# Schematic.net
KiCad netlist of a schematic drawn in EAGLE
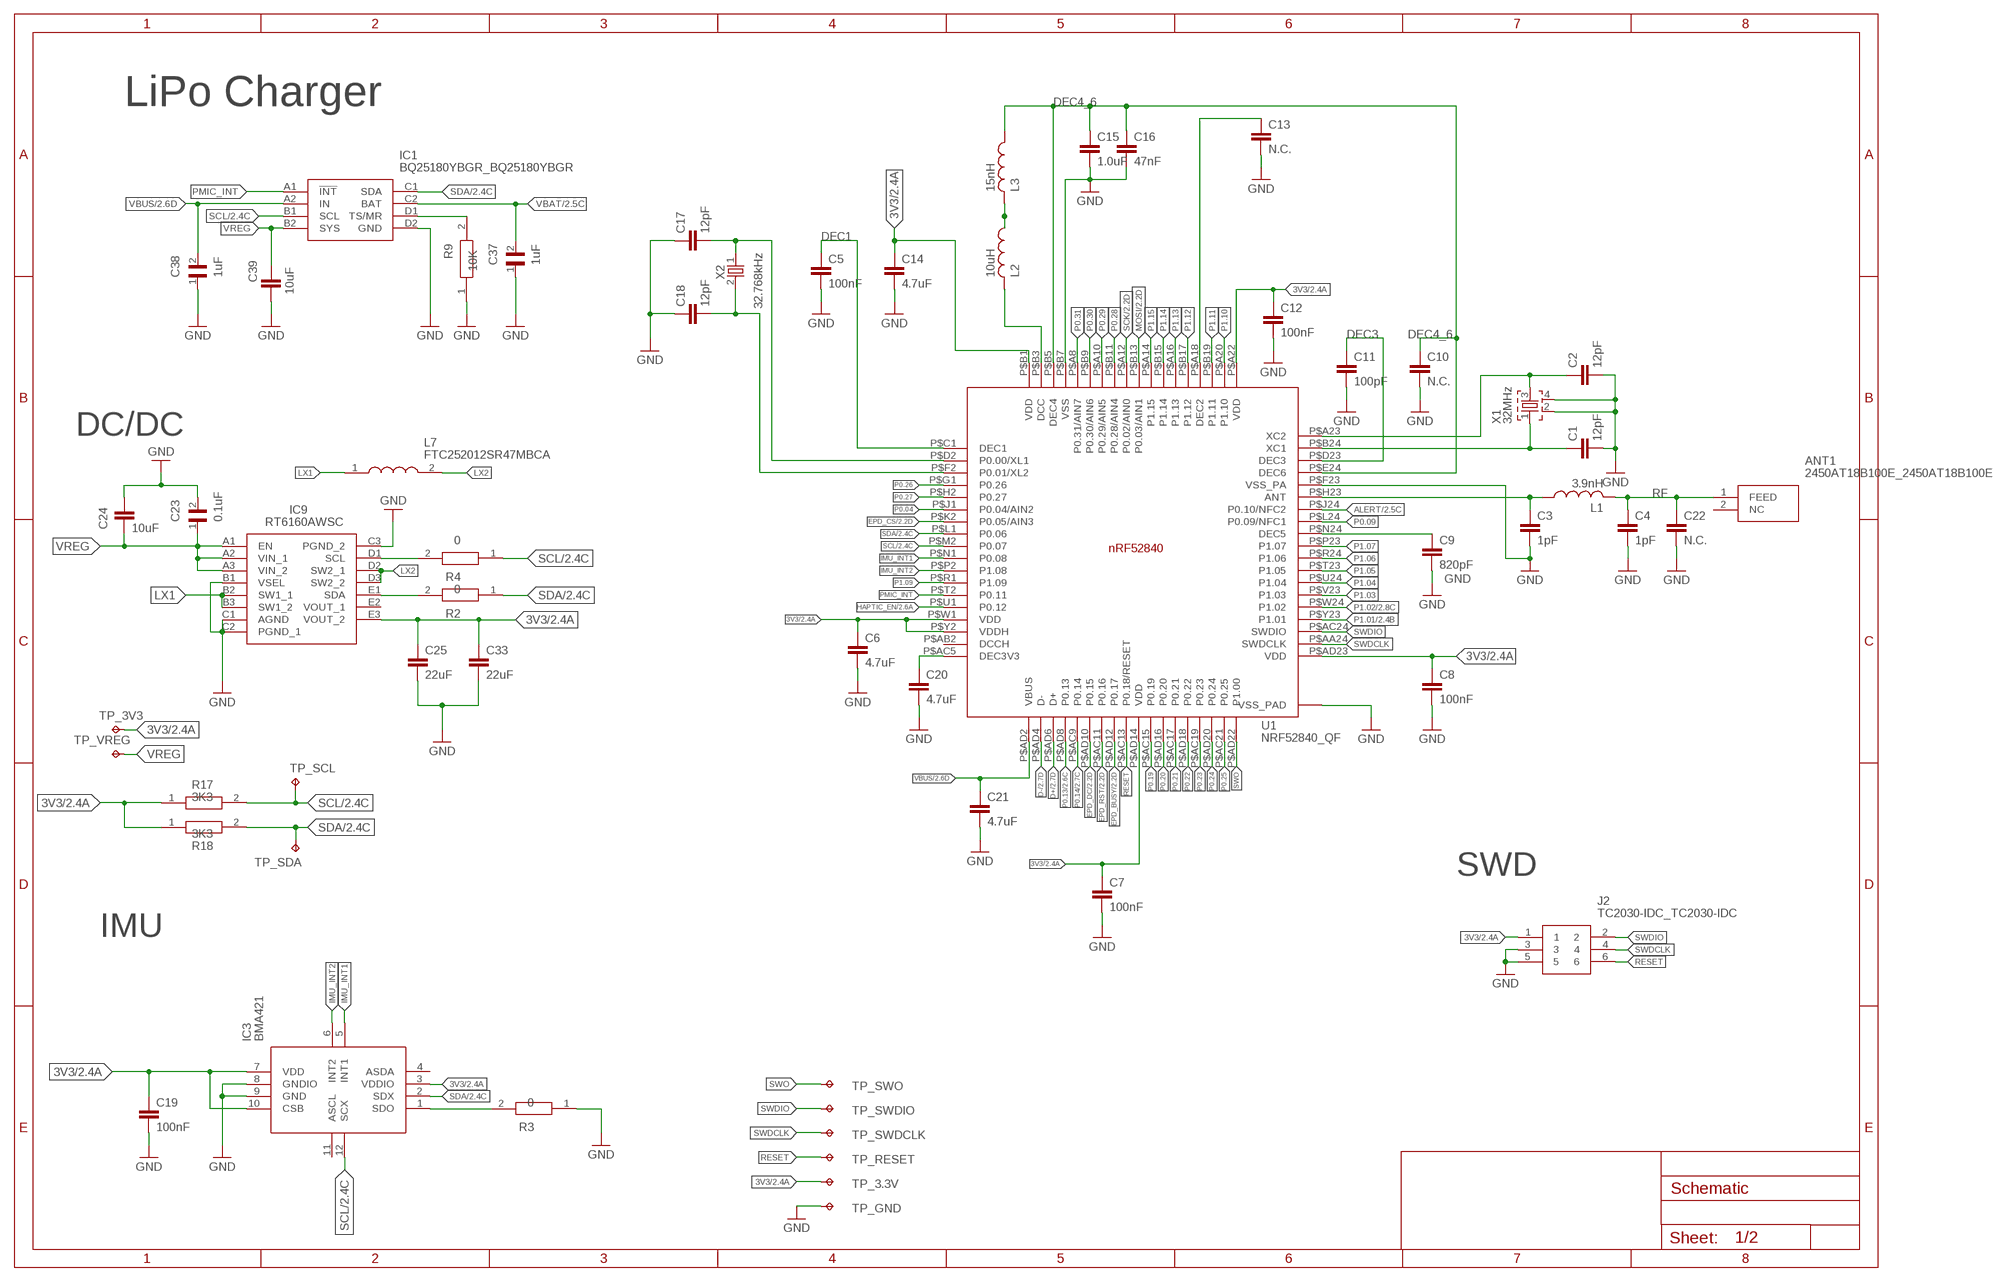
[diagram p0: schematic, sheet 1]
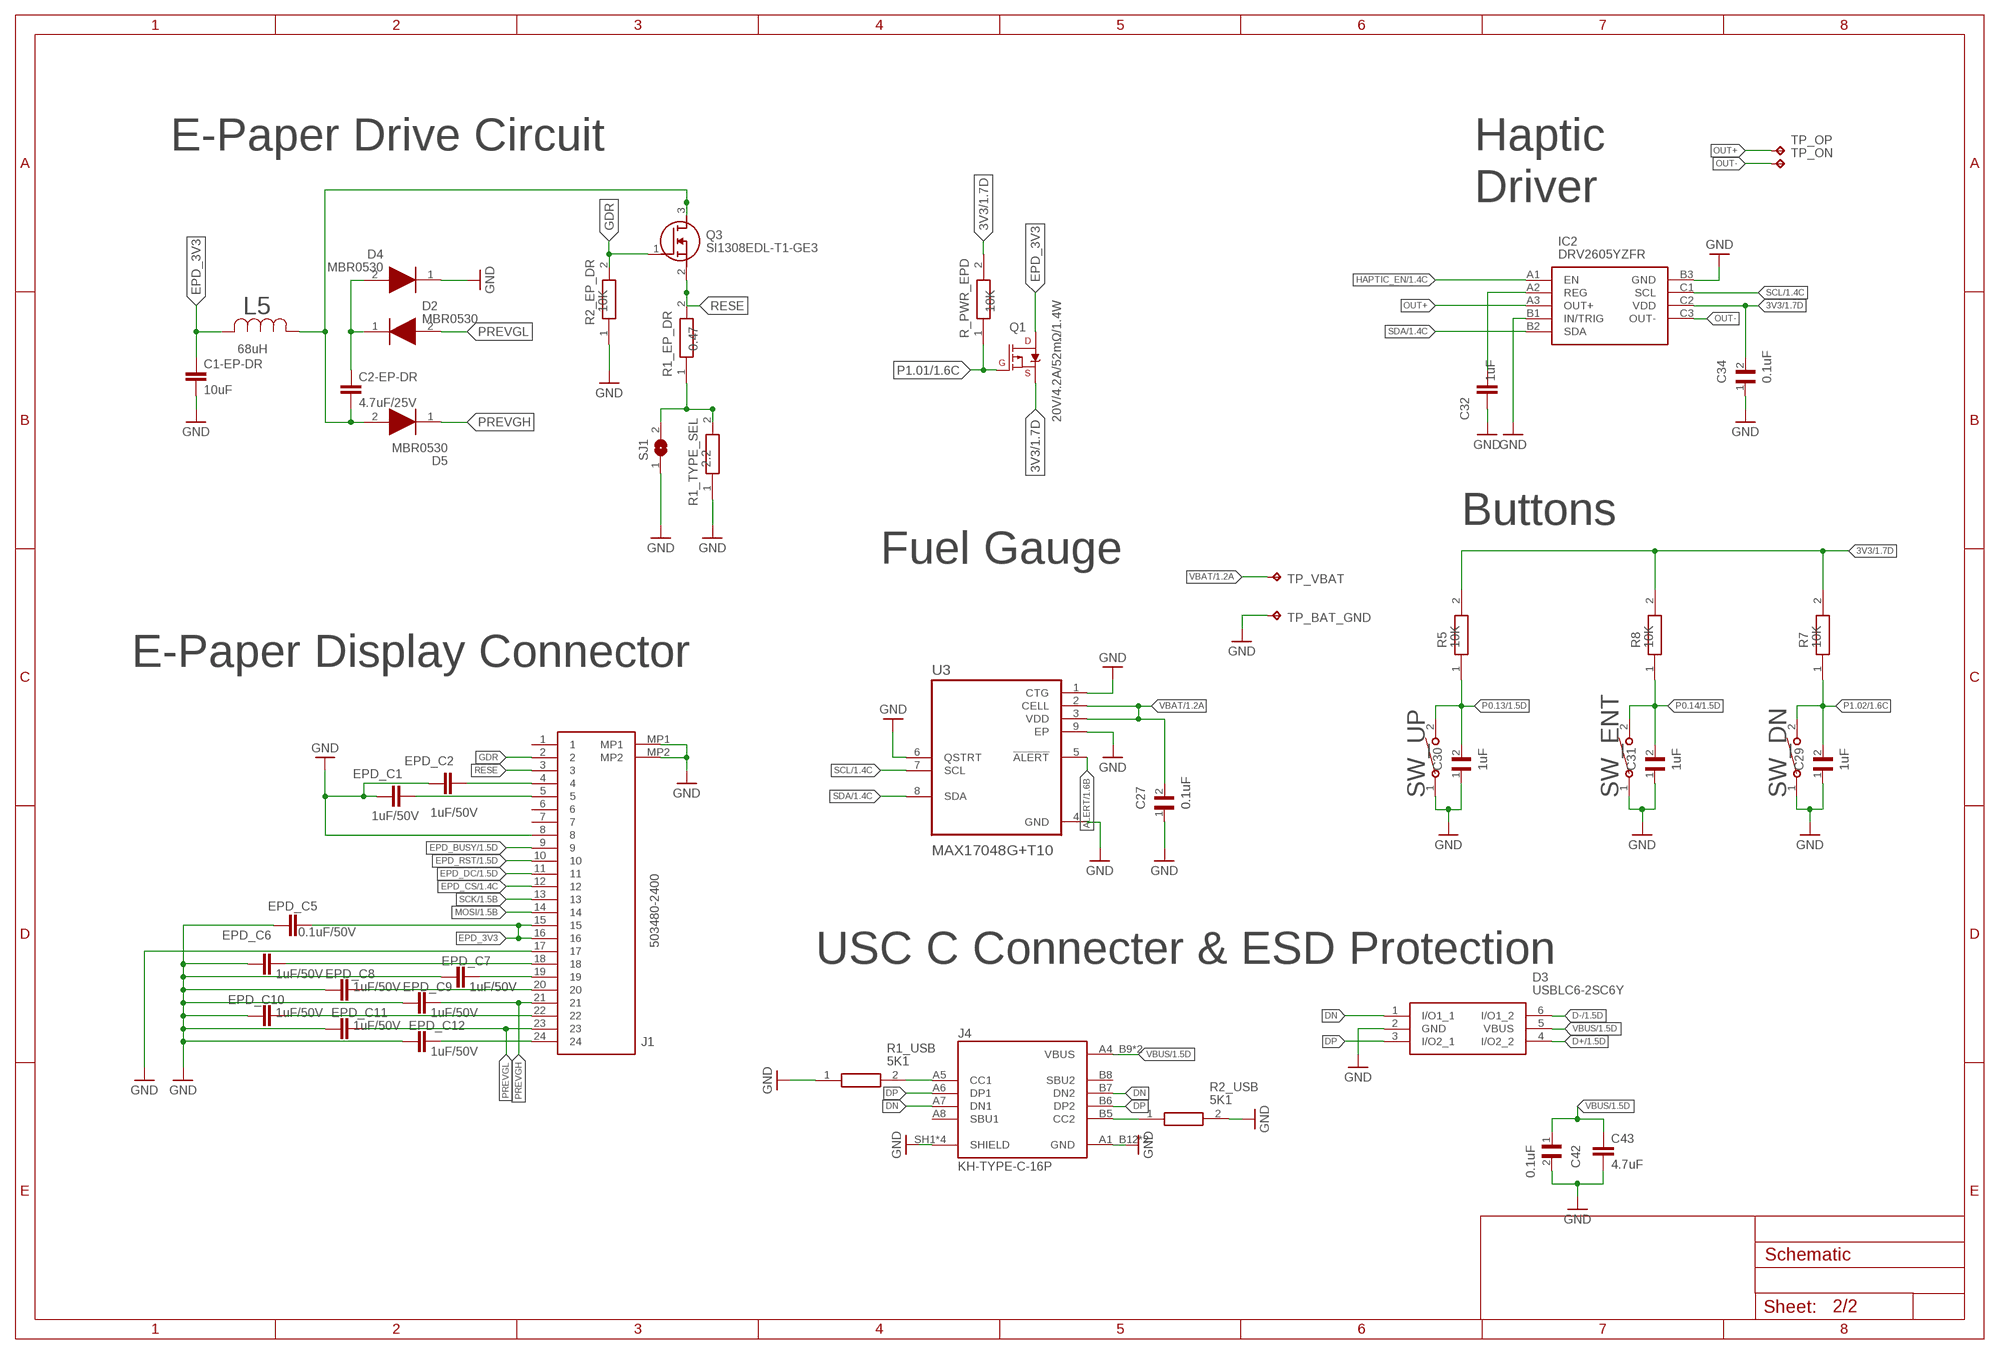
[diagram p1: schematic, sheet 2]

(export (version "E")
  (design (tool "Eeschema 10.0.6"))
  (components
    (comp (ref "ANT1")
      (value "2450AT18B100E_2450AT18B100E")
      (footprint "eagle-import:2450AT18B100E_ANTC3216X140N")
      (fields
        (field (name "ARROW_PART_NUMBER") "2450AT18B100E")
        (field (name "MOUSER_PART_NUMBER") "609-2450AT18B100E")
      )
      (libsource (lib "eagle-import") (part "2450AT18B100E_2450AT18B100E"))
    )
    (comp (ref "C1")
      (value "12pF")
      (footprint "eagle-import:NORDIC_NRF_3_RESC0201_L")
      (libsource (lib "eagle-import") (part "NORDIC_NRF_3_CAPACITOR_0201_L"))
    )
    (comp (ref "C2")
      (value "12pF")
      (footprint "eagle-import:NORDIC_NRF_3_RESC0201_L")
      (libsource (lib "eagle-import") (part "NORDIC_NRF_3_CAPACITOR_0201_L"))
    )
    (comp (ref "C3")
      (value "1pF")
      (footprint "eagle-import:NORDIC_NRF_3_RESC0201_L")
      (libsource (lib "eagle-import") (part "NORDIC_NRF_3_CAPACITOR_0201_L"))
    )
    (comp (ref "C4")
      (value "1pF")
      (footprint "eagle-import:NORDIC_NRF_3_RESC0201_L")
      (libsource (lib "eagle-import") (part "NORDIC_NRF_3_CAPACITOR_0201_L"))
    )
    (comp (ref "C5")
      (value "100nF")
      (footprint "eagle-import:NORDIC_NRF_3_RESC0201_L")
      (libsource (lib "eagle-import") (part "NORDIC_NRF_3_CAPACITOR_0201_L"))
    )
    (comp (ref "C6")
      (value "4.7uF")
      (footprint "eagle-import:NORDIC_NRF_3_RESC0402_L")
      (libsource (lib "eagle-import") (part "NORDIC_NRF_3_CAPACITOR_0402_L"))
    )
    (comp (ref "C7")
      (value "100nF")
      (footprint "eagle-import:NORDIC_NRF_3_RESC0201_L")
      (libsource (lib "eagle-import") (part "NORDIC_NRF_3_CAPACITOR_0201_L"))
    )
    (comp (ref "C8")
      (value "100nF")
      (footprint "eagle-import:NORDIC_NRF_3_RESC0201_L")
      (libsource (lib "eagle-import") (part "NORDIC_NRF_3_CAPACITOR_0201_L"))
    )
    (comp (ref "C9")
      (value "820pF")
      (footprint "eagle-import:NORDIC_NRF_3_RESC0201_L")
      (libsource (lib "eagle-import") (part "NORDIC_NRF_3_CAPACITOR_0201_L"))
    )
    (comp (ref "C10")
      (value "N.C.")
      (footprint "eagle-import:NORDIC_NRF_3_RESC0201_L")
      (libsource (lib "eagle-import") (part "NORDIC_NRF_3_CAPACITOR_0201_L"))
    )
    (comp (ref "C11")
      (value "100pF")
      (footprint "eagle-import:NORDIC_NRF_3_RESC0201_L")
      (libsource (lib "eagle-import") (part "NORDIC_NRF_3_CAPACITOR_0201_L"))
    )
    (comp (ref "C12")
      (value "100nF")
      (footprint "eagle-import:NORDIC_NRF_3_RESC0201_L")
      (libsource (lib "eagle-import") (part "NORDIC_NRF_3_CAPACITOR_0201_L"))
    )
    (comp (ref "C13")
      (value "N.C.")
      (footprint "eagle-import:NORDIC_NRF_3_RESC0201_L")
      (libsource (lib "eagle-import") (part "NORDIC_NRF_3_CAPACITOR_0201_L"))
    )
    (comp (ref "C14")
      (value "4.7uF")
      (footprint "eagle-import:NORDIC_NRF_3_RESC0402_L")
      (libsource (lib "eagle-import") (part "NORDIC_NRF_3_CAPACITOR_0402_L"))
    )
    (comp (ref "C15")
      (value "1.0uF")
      (footprint "eagle-import:NORDIC_NRF_3_RESC0402_L")
      (libsource (lib "eagle-import") (part "NORDIC_NRF_3_CAPACITOR_0402_L"))
    )
    (comp (ref "C16")
      (value "47nF")
      (footprint "eagle-import:NORDIC_NRF_3_RESC0201_L")
      (libsource (lib "eagle-import") (part "NORDIC_NRF_3_CAPACITOR_0201_L"))
    )
    (comp (ref "C17")
      (value "12pF")
      (footprint "eagle-import:NORDIC_NRF_3_RESC0201_L")
      (libsource (lib "eagle-import") (part "NORDIC_NRF_3_CAPACITOR_0201_L"))
    )
    (comp (ref "C18")
      (value "12pF")
      (footprint "eagle-import:NORDIC_NRF_3_RESC0201_L")
      (libsource (lib "eagle-import") (part "NORDIC_NRF_3_CAPACITOR_0201_L"))
    )
    (comp (ref "C19")
      (value "100nF")
      (footprint "eagle-import:NORDIC_NRF_3_RESC0201_L")
      (libsource (lib "eagle-import") (part "NORDIC_NRF_3_CAPACITOR_0201_L"))
    )
    (comp (ref "C20")
      (value "4.7uF")
      (footprint "eagle-import:NORDIC_NRF_3_RESC0402_L")
      (libsource (lib "eagle-import") (part "NORDIC_NRF_3_CAPACITOR_0402_L"))
    )
    (comp (ref "C21")
      (value "4.7uF")
      (footprint "eagle-import:NORDIC_NRF_3_RESC0402_L")
      (libsource (lib "eagle-import") (part "NORDIC_NRF_3_CAPACITOR_0402_L"))
    )
    (comp (ref "C22")
      (value "N.C.")
      (footprint "eagle-import:NORDIC_NRF_3_RESC0201_L")
      (libsource (lib "eagle-import") (part "NORDIC_NRF_3_CAPACITOR_0201_L"))
    )
    (comp (ref "C23")
      (value "0.1uF")
      (footprint "eagle-import:GRM011R60J152KE01L_2_CAPC0201X13N")
      (fields (field (name "MF") "Murata") (field (name "MP") "GRM011R60J152KE01L"))
      (libsource (lib "eagle-import") (part "GRM011R60J152KE01L_2_GRM011R60J152KE01L"))
    )
    (comp (ref "C24")
      (value "10uF")
      (footprint "eagle-import:NORDIC_NRF_3_RESC0402_L")
      (libsource (lib "eagle-import") (part "NORDIC_NRF_3_CAPACITOR_0402_L"))
    )
    (comp (ref "C25")
      (value "22uF")
      (footprint "eagle-import:NORDIC_NRF_3_RESC0402_L")
      (libsource (lib "eagle-import") (part "NORDIC_NRF_3_CAPACITOR_0402_L"))
    )
    (comp (ref "C33")
      (value "22uF")
      (footprint "eagle-import:NORDIC_NRF_3_RESC0402_L")
      (libsource (lib "eagle-import") (part "NORDIC_NRF_3_CAPACITOR_0402_L"))
    )
    (comp (ref "C37")
      (value "1uF")
      (footprint "eagle-import:GRM011R60J152KE01L_2_CAPC0201X13N")
      (fields (field (name "MF") "Murata") (field (name "MP") "GRM011R60J152KE01L"))
      (libsource (lib "eagle-import") (part "GRM011R60J152KE01L_2_GRM011R60J152KE01L"))
    )
    (comp (ref "C38")
      (value "1uF")
      (footprint "eagle-import:GRM011R60J152KE01L_2_CAPC0201X13N")
      (fields (field (name "MF") "Murata") (field (name "MP") "GRM011R60J152KE01L"))
      (libsource (lib "eagle-import") (part "GRM011R60J152KE01L_2_GRM011R60J152KE01L"))
    )
    (comp (ref "C39")
      (value "10uF")
      (footprint "eagle-import:NORDIC_NRF_3_RESC0402_N")
      (libsource (lib "eagle-import") (part "NORDIC_NRF_3_CAPACITOR_0402_N"))
    )
    (comp (ref "IC1")
      (value "BQ25180YBGR_BQ25180YBGR")
      (footprint "eagle-import:BQ25180YBGR_BGA8C40P2X4_100X155X50")
      (fields
        (field (name "ARROW_PART_NUMBER") "BQ25180YBGR")
        (field (name "MOUSER_PART_NUMBER") "595-BQ25180YBGR")
      )
      (libsource (lib "eagle-import") (part "BQ25180YBGR_BQ25180YBGR"))
    )
    (comp (ref "IC3")
      (value "BMA421")
      (footprint "eagle-import:BMA423_BMA423")
      (fields (field (name "ARROW_PART_NUMBER") "BMA423") (field (name "MOUSER_PART_NUMBER") "262-BMA423"))
      (libsource (lib "eagle-import") (part "BMA423_BMA423"))
    )
    (comp (ref "IC9")
      (value "RT6160AWSC")
      (footprint "eagle-import:RT6160AWSC_BGA15C40P3X5_140X230X60")
      (fields (field (name "MOUSER_PART_NUMBER") "835-RT6160AWSC"))
      (libsource (lib "eagle-import") (part "RT6160AWSC_RT6160AWSC"))
    )
    (comp (ref "J2")
      (value "TC2030-IDC_TC2030-IDC")
      (footprint "eagle-import:TC2030-IDC_TC2030IDC")
      (fields (field (name "MANUFACTURER_PART_NUMBER") "TC2030-IDC"))
      (libsource (lib "eagle-import") (part "TC2030-IDC_TC2030-IDC"))
    )
    (comp (ref "L1")
      (value "3.9nH")
      (footprint "eagle-import:NORDIC_NRF_2_RESC0402_L")
      (libsource (lib "eagle-import") (part "NORDIC_NRF_2_INDUCTOR_0402_L"))
    )
    (comp (ref "L2")
      (value "10uH")
      (footprint "eagle-import:NORDIC_NRF_2_RESC0402_L")
      (libsource (lib "eagle-import") (part "NORDIC_NRF_2_INDUCTOR_0402_L"))
    )
    (comp (ref "L3")
      (value "15nH")
      (footprint "eagle-import:NORDIC_NRF_2_RESC0402_L")
      (libsource (lib "eagle-import") (part "NORDIC_NRF_2_INDUCTOR_0402_L"))
    )
    (comp (ref "L7")
      (value "FTC252012SR47MBCA")
      (footprint "eagle-import:MLP2016SR47MT0S1_INDC2016X100N")
      (libsource (lib "eagle-import") (part "MLP2016SR47MT0S1_FTC252012SR47MBCA"))
    )
    (comp (ref "R2")
      (value "0")
      (footprint "eagle-import:ERA-1AEB3401C_0201")
      (libsource (lib "eagle-import") (part "ERA-1AEB3401C_CPF0201D7K68C1"))
    )
    (comp (ref "R3")
      (value "0")
      (footprint "eagle-import:CPF0201D7K68C1_0201")
      (libsource (lib "eagle-import") (part "CPF0201D7K68C1_CPF0201D7K68C1"))
    )
    (comp (ref "R4")
      (value "0")
      (footprint "eagle-import:ERA-1AEB3401C_0201")
      (libsource (lib "eagle-import") (part "ERA-1AEB3401C_CPF0201D7K68C1"))
    )
    (comp (ref "R9")
      (value "10K")
      (footprint "eagle-import:CPF0201D7K68C1_0201")
      (libsource (lib "eagle-import") (part "CPF0201D7K68C1_CPF0201D7K68C1"))
    )
    (comp (ref "R17")
      (value "3K3")
      (footprint "eagle-import:CPF0201D7K68C1_0201")
      (libsource (lib "eagle-import") (part "CPF0201D7K68C1_CPF0201D7K68C1"))
    )
    (comp (ref "R18")
      (value "3K3")
      (footprint "eagle-import:CPF0201D7K68C1_0201")
      (libsource (lib "eagle-import") (part "CPF0201D7K68C1_CPF0201D7K68C1"))
    )
    (comp (ref "TP_3.3V")
      (value "HECTOR_WATCH_1_TPTP20R")
      (footprint "eagle-import:HECTOR_WATCH_1_TP20R")
      (libsource (lib "eagle-import") (part "HECTOR_WATCH_1_TPTP20R"))
    )
    (comp (ref "TP_3V3")
      (value "HECTOR_WATCH_1_TPTP20R")
      (footprint "eagle-import:HECTOR_WATCH_1_TP20R")
      (libsource (lib "eagle-import") (part "HECTOR_WATCH_1_TPTP20R"))
    )
    (comp (ref "TP_GND")
      (value "HECTOR_WATCH_1_TPTP20R")
      (footprint "eagle-import:HECTOR_WATCH_1_TP20R")
      (libsource (lib "eagle-import") (part "HECTOR_WATCH_1_TPTP20R"))
    )
    (comp (ref "TP_RESET")
      (value "HECTOR_WATCH_1_TPTP20R")
      (footprint "eagle-import:HECTOR_WATCH_1_TP20R")
      (libsource (lib "eagle-import") (part "HECTOR_WATCH_1_TPTP20R"))
    )
    (comp (ref "TP_SCL")
      (value "HECTOR_WATCH_1_TPTP20R")
      (footprint "eagle-import:HECTOR_WATCH_1_TP20R")
      (libsource (lib "eagle-import") (part "HECTOR_WATCH_1_TPTP20R"))
    )
    (comp (ref "TP_SDA")
      (value "HECTOR_WATCH_1_TPTP20R")
      (footprint "eagle-import:HECTOR_WATCH_1_TP20R")
      (libsource (lib "eagle-import") (part "HECTOR_WATCH_1_TPTP20R"))
    )
    (comp (ref "TP_SWDCLK")
      (value "HECTOR_WATCH_1_TPTP20R")
      (footprint "eagle-import:HECTOR_WATCH_1_TP20R")
      (libsource (lib "eagle-import") (part "HECTOR_WATCH_1_TPTP20R"))
    )
    (comp (ref "TP_SWDIO")
      (value "HECTOR_WATCH_1_TPTP20R")
      (footprint "eagle-import:HECTOR_WATCH_1_TP20R")
      (libsource (lib "eagle-import") (part "HECTOR_WATCH_1_TPTP20R"))
    )
    (comp (ref "TP_SWO")
      (value "HECTOR_WATCH_1_TPTP20R")
      (footprint "eagle-import:HECTOR_WATCH_1_TP20R")
      (libsource (lib "eagle-import") (part "HECTOR_WATCH_1_TPTP20R"))
    )
    (comp (ref "TP_VREG")
      (value "HECTOR_WATCH_1_TPTP20R")
      (footprint "eagle-import:HECTOR_WATCH_1_TP20R")
      (libsource (lib "eagle-import") (part "HECTOR_WATCH_1_TPTP20R"))
    )
    (comp (ref "U1")
      (value "NRF52840_QF")
      (footprint "eagle-import:NORDIC_NRF_4_AQFN50P700X700X85_HS-74N")
      (libsource (lib "eagle-import") (part "NORDIC_NRF_4_NRF52840_QF"))
    )
    (comp (ref "X1")
      (value "32MHz")
      (footprint "eagle-import:NORDIC_NRF_BT-XTAL_2016_N")
      (libsource (lib "eagle-import") (part "NORDIC_NRF_XTAL_32MHZ"))
    )
    (comp (ref "X2")
      (value "32.768kHz")
      (footprint "eagle-import:NORDIC_NRF_1_XTAL_3215_N")
      (libsource (lib "eagle-import") (part "NORDIC_NRF_1_XTAL_32KHZ"))
    )
    (comp (ref "C1-EP-DR")
      (value "10uF")
      (footprint "eagle-import:NORDIC_NRF_3_RESC0402_L")
      (libsource (lib "eagle-import") (part "NORDIC_NRF_3_CAPACITOR_0402_L"))
    )
    (comp (ref "C2-EP-DR")
      (value "4.7uF/25V")
      (footprint "eagle-import:NORDIC_NRF_3_RESC0201_L")
      (libsource (lib "eagle-import") (part "NORDIC_NRF_3_CAPACITOR_0201_L"))
    )
    (comp (ref "C27")
      (value "0.1uF")
      (footprint "eagle-import:GRM011R60J152KE01L_2_CAPC0201X13N")
      (fields (field (name "MF") "Murata") (field (name "MP") "GRM011R60J152KE01L"))
      (libsource (lib "eagle-import") (part "GRM011R60J152KE01L_2_GRM011R60J152KE01L"))
    )
    (comp (ref "C29")
      (value "1uF")
      (footprint "eagle-import:GRM011R60J152KE01L_2_CAPC0201X13N")
      (fields (field (name "MF") "Murata") (field (name "MP") "GRM011R60J152KE01L"))
      (libsource (lib "eagle-import") (part "GRM011R60J152KE01L_2_GRM011R60J152KE01L"))
    )
    (comp (ref "C30")
      (value "1uF")
      (footprint "eagle-import:GRM011R60J152KE01L_2_CAPC0201X13N")
      (fields (field (name "MF") "Murata") (field (name "MP") "GRM011R60J152KE01L"))
      (libsource (lib "eagle-import") (part "GRM011R60J152KE01L_2_GRM011R60J152KE01L"))
    )
    (comp (ref "C31")
      (value "1uF")
      (footprint "eagle-import:GRM011R60J152KE01L_2_CAPC0201X13N")
      (fields (field (name "MF") "Murata") (field (name "MP") "GRM011R60J152KE01L"))
      (libsource (lib "eagle-import") (part "GRM011R60J152KE01L_2_GRM011R60J152KE01L"))
    )
    (comp (ref "C32")
      (value "1uF")
      (footprint "eagle-import:NORDIC_NRF_3_RESC0402_L")
      (libsource (lib "eagle-import") (part "NORDIC_NRF_3_CAPACITOR_0402_L"))
    )
    (comp (ref "C34")
      (value "0.1uF")
      (footprint "eagle-import:GRM011R60J152KE01L_2_CAPC0201X13N")
      (fields (field (name "MF") "Murata") (field (name "MP") "GRM011R60J152KE01L"))
      (libsource (lib "eagle-import") (part "GRM011R60J152KE01L_2_GRM011R60J152KE01L"))
    )
    (comp (ref "C42")
      (value "0.1uF")
      (footprint "eagle-import:GRM011R60J152KE01L_2_CAPC0201X13N")
      (fields (field (name "MF") "Murata") (field (name "MP") "GRM011R60J152KE01L"))
      (libsource (lib "eagle-import") (part "GRM011R60J152KE01L_2_GRM011R60J152KE01L"))
    )
    (comp (ref "C43")
      (value "4.7uF")
      (footprint "eagle-import:NORDIC_NRF_3_RESC0402_L")
      (libsource (lib "eagle-import") (part "NORDIC_NRF_3_CAPACITOR_0402_L"))
    )
    (comp (ref "D2")
      (value "MBR0530")
      (footprint "eagle-import:ESP32_C6_LIBRARY_5_SOD3716X135N")
      (fields (field (name "MF") "ON Semiconductor"))
      (libsource (lib "eagle-import") (part "ESP32_C6_LIBRARY_5_MBR0530"))
    )
    (comp (ref "D3")
      (value "USBLC6-2SC6Y")
      (footprint "eagle-import:ESP32_C6_LIBRARY_3_SOT95P280X145-6N")
      (fields (field (name "MF") "STMicroelectronics"))
      (libsource (lib "eagle-import") (part "ESP32_C6_LIBRARY_3_USBLC6-2SC6Y"))
    )
    (comp (ref "D4")
      (value "MBR0530")
      (footprint "eagle-import:ESP32_C6_LIBRARY_5_SOD3716X135N")
      (fields (field (name "MF") "ON Semiconductor"))
      (libsource (lib "eagle-import") (part "ESP32_C6_LIBRARY_5_MBR0530"))
    )
    (comp (ref "D5")
      (value "MBR0530")
      (footprint "eagle-import:ESP32_C6_LIBRARY_5_SOD3716X135N")
      (fields (field (name "MF") "ON Semiconductor"))
      (libsource (lib "eagle-import") (part "ESP32_C6_LIBRARY_5_MBR0530"))
    )
    (comp (ref "EPD_C1")
      (value "1uF/50V")
      (footprint "eagle-import:NORDIC_NRF_3_RESC0402_L")
      (libsource (lib "eagle-import") (part "NORDIC_NRF_3_CAPACITOR_0402_L"))
    )
    (comp (ref "EPD_C2")
      (value "1uF/50V")
      (footprint "eagle-import:NORDIC_NRF_3_RESC0402_L")
      (libsource (lib "eagle-import") (part "NORDIC_NRF_3_CAPACITOR_0402_L"))
    )
    (comp (ref "EPD_C5")
      (value "0.1uF/50V")
      (footprint "eagle-import:NORDIC_NRF_3_RESC0402_L")
      (libsource (lib "eagle-import") (part "NORDIC_NRF_3_CAPACITOR_0402_L"))
    )
    (comp (ref "EPD_C6")
      (value "1uF/50V")
      (footprint "eagle-import:NORDIC_NRF_3_RESC0402_L")
      (libsource (lib "eagle-import") (part "NORDIC_NRF_3_CAPACITOR_0402_L"))
    )
    (comp (ref "EPD_C7")
      (value "1uF/50V")
      (footprint "eagle-import:NORDIC_NRF_3_RESC0402_L")
      (libsource (lib "eagle-import") (part "NORDIC_NRF_3_CAPACITOR_0402_L"))
    )
    (comp (ref "EPD_C8")
      (value "1uF/50V")
      (footprint "eagle-import:NORDIC_NRF_3_RESC0402_L")
      (libsource (lib "eagle-import") (part "NORDIC_NRF_3_CAPACITOR_0402_L"))
    )
    (comp (ref "EPD_C9")
      (value "1uF/50V")
      (footprint "eagle-import:NORDIC_NRF_3_RESC0402_L")
      (libsource (lib "eagle-import") (part "NORDIC_NRF_3_CAPACITOR_0402_L"))
    )
    (comp (ref "EPD_C10")
      (value "1uF/50V")
      (footprint "eagle-import:NORDIC_NRF_3_RESC0402_L")
      (libsource (lib "eagle-import") (part "NORDIC_NRF_3_CAPACITOR_0402_L"))
    )
    (comp (ref "EPD_C11")
      (value "1uF/50V")
      (footprint "eagle-import:NORDIC_NRF_3_RESC0402_L")
      (libsource (lib "eagle-import") (part "NORDIC_NRF_3_CAPACITOR_0402_L"))
    )
    (comp (ref "EPD_C12")
      (value "1uF/50V")
      (footprint "eagle-import:NORDIC_NRF_3_RESC0402_L")
      (libsource (lib "eagle-import") (part "NORDIC_NRF_3_CAPACITOR_0402_L"))
    )
    (comp (ref "IC2")
      (value "DRV2605YZFR")
      (footprint "eagle-import:DRV2605YZFR_BGA9C50P3X3_144X144X62")
      (libsource (lib "eagle-import") (part "DRV2605YZFR_DRV2605YZFR"))
    )
    (comp (ref "J1")
      (value "503480-2400")
      (footprint "eagle-import:503480-2400_5034802400")
      (fields (field (name "MOUSER_PART_NUMBER") "538-503480-2400"))
      (libsource (lib "eagle-import") (part "503480-2400_503480-2400"))
    )
    (comp (ref "J4")
      (value "KH-TYPE-C-16P")
      (footprint "eagle-import:KH-TYPE-C-16P_KINGHELM_KH-TYPE-C-16P")
      (fields (field (name "MF") "kinghelm"))
      (libsource (lib "eagle-import") (part "KH-TYPE-C-16P_KH-TYPE-C-16P"))
    )
    (comp (ref "L5")
      (value "68uH")
      (footprint "eagle-import:ESP32_C6_LIBRARY_2_IND_4828-WE-TPC_WRE")
      (fields
        (field (name "MANUFACTURER_PART_NUMBER") "744043680")
        (field (name "COPYRIGHT") "Copyright (C) 2024 Ultra Librarian. All rights reserved.")
      )
      (libsource (lib "eagle-import") (part "ESP32_C6_LIBRARY_2_744043680IND_4828-WE-TPC_WRE"))
    )
    (comp (ref "Q1")
      (value "20V/4.2A/52mΩ/1.4W")
      (footprint "eagle-import:ESP32_C6_LIBRARY_4_ESP32_C6_LIBRARY_4_ESP32_C6_LIBRARY_4_ESP32_C6_LIBRARY_4_ESP32_WROVER_SPARKFUN-DISCRETESEMI_SOT23-3")
      (libsource (lib "eagle-import") (part "ESP32_C6_LIBRARY_4_ESP32_WROVER_SPARKFUN-DISCRETESEMI_MOSFET_PCH-DMG2305UX-7"))
    )
    (comp (ref "Q3")
      (value "SI1308EDL-T1-GE3")
      (footprint "eagle-import:ESP32_C6_LIBRARY_6_SOT65P210X110-3N")
      (fields (field (name "MF") "Vishay Siliconix"))
      (libsource (lib "eagle-import") (part "ESP32_C6_LIBRARY_6_SI1308EDL-T1-GE3"))
    )
    (comp (ref "R1_EP_DR")
      (value "0.47")
      (footprint "eagle-import:CPF0201D7K68C1_0201")
      (libsource (lib "eagle-import") (part "CPF0201D7K68C1_CPF0201D7K68C1"))
    )
    (comp (ref "R1_TYPE_SEL")
      (value "2.2")
      (footprint "eagle-import:CPF0201D7K68C1_0201")
      (libsource (lib "eagle-import") (part "CPF0201D7K68C1_CPF0201D7K68C1"))
    )
    (comp (ref "R1_USB")
      (value "5K1")
      (footprint "eagle-import:ERA-1AEB3401C_0201")
      (libsource (lib "eagle-import") (part "ERA-1AEB3401C_CPF0201D7K68C1"))
    )
    (comp (ref "R2_EP_DR")
      (value "10K")
      (footprint "eagle-import:CPF0201D7K68C1_0201")
      (libsource (lib "eagle-import") (part "CPF0201D7K68C1_CPF0201D7K68C1"))
    )
    (comp (ref "R2_USB")
      (value "5K1")
      (footprint "eagle-import:CPF0201D7K68C1_0201")
      (libsource (lib "eagle-import") (part "CPF0201D7K68C1_CPF0201D7K68C1"))
    )
    (comp (ref "R5")
      (value "10K")
      (footprint "eagle-import:ERA-1AEB3401C_0201")
      (libsource (lib "eagle-import") (part "ERA-1AEB3401C_CPF0201D7K68C1"))
    )
    (comp (ref "R7")
      (value "10K")
      (footprint "eagle-import:ERA-1AEB3401C_0201")
      (libsource (lib "eagle-import") (part "ERA-1AEB3401C_CPF0201D7K68C1"))
    )
    (comp (ref "R8")
      (value "10K")
      (footprint "eagle-import:ERA-1AEB3401C_0201")
      (libsource (lib "eagle-import") (part "ERA-1AEB3401C_CPF0201D7K68C1"))
    )
    (comp (ref "R_PWR_EPD")
      (value "10K")
      (footprint "eagle-import:CPF0201D7K68C1_0201")
      (libsource (lib "eagle-import") (part "CPF0201D7K68C1_CPF0201D7K68C1"))
    )
    (comp (ref "SJ1")
      (value "ESP32_C6_LIBRARY_7_JUMPER_SJ")
      (footprint "eagle-import:ESP32_C6_LIBRARY_7_JUMPER_SJ")
      (libsource (lib "eagle-import") (part "ESP32_C6_LIBRARY_7_JUMPER_SJ"))
    )
    (comp (ref "SW_DN")
      (value "2025-10-22_07-23-44_LIBRARY_EVP-AKE31ASW_EVP-AKE31A_PAN")
      (footprint "eagle-import:2025-10-22_07-23-44_LIBRARY_SW_EVP-AKE31A_PAN")
      (fields
        (field (name "MANUFACTURER_PART_NUMBER") "EVP-AKE31A")
        (field (name "COPYRIGHT") "Copyright (C) 2025 Ultra Librarian. All rights reserved.")
      )
      (libsource (lib "eagle-import") (part "2025-10-22_07-23-44_LIBRARY_EVP-AKE31ASW_EVP-AKE31A_PAN"))
    )
    (comp (ref "SW_ENT")
      (value "2025-10-22_07-23-44_LIBRARY_EVP-AKE31ASW_EVP-AKE31A_PAN")
      (footprint "eagle-import:2025-10-22_07-23-44_LIBRARY_SW_EVP-AKE31A_PAN")
      (fields
        (field (name "MANUFACTURER_PART_NUMBER") "EVP-AKE31A")
        (field (name "COPYRIGHT") "Copyright (C) 2025 Ultra Librarian. All rights reserved.")
      )
      (libsource (lib "eagle-import") (part "2025-10-22_07-23-44_LIBRARY_EVP-AKE31ASW_EVP-AKE31A_PAN"))
    )
    (comp (ref "SW_UP")
      (value "2025-10-22_07-23-44_LIBRARY_EVP-AKE31ASW_EVP-AKE31A_PAN")
      (footprint "eagle-import:2025-10-22_07-23-44_LIBRARY_SW_EVP-AKE31A_PAN")
      (fields
        (field (name "MANUFACTURER_PART_NUMBER") "EVP-AKE31A")
        (field (name "COPYRIGHT") "Copyright (C) 2025 Ultra Librarian. All rights reserved.")
      )
      (libsource (lib "eagle-import") (part "2025-10-22_07-23-44_LIBRARY_EVP-AKE31ASW_EVP-AKE31A_PAN"))
    )
    (comp (ref "TP_BAT_GND")
      (value "HECTOR_WATCH_1_TPTP20R")
      (footprint "eagle-import:HECTOR_WATCH_1_TP20R")
      (libsource (lib "eagle-import") (part "HECTOR_WATCH_1_TPTP20R"))
    )
    (comp (ref "TP_ON")
      (value "HECTOR_WATCH_1_TPTP20R")
      (footprint "eagle-import:HECTOR_WATCH_1_TP20R")
      (libsource (lib "eagle-import") (part "HECTOR_WATCH_1_TPTP20R"))
    )
    (comp (ref "TP_OP")
      (value "HECTOR_WATCH_1_TPTP20R")
      (footprint "eagle-import:HECTOR_WATCH_1_TP20R")
      (libsource (lib "eagle-import") (part "HECTOR_WATCH_1_TPTP20R"))
    )
    (comp (ref "TP_VBAT")
      (value "HECTOR_WATCH_1_TPTP20R")
      (footprint "eagle-import:HECTOR_WATCH_1_TP20R")
      (libsource (lib "eagle-import") (part "HECTOR_WATCH_1_TPTP20R"))
    )
    (comp (ref "U3")
      (value "MAX17048G+T10")
      (footprint "eagle-import:ESP32_C6_LIBRARY_SON50P200X200X80-9N")
      (fields (field (name "MF") "Analog Devices"))
      (libsource (lib "eagle-import") (part "ESP32_C6_LIBRARY_MAX17048G+T10"))
    )
  )
  (nets
    (net (code "1") (name "3V3{slash}1.7D") (class "Default")
      (node (ref "C34") (pin "2") (pinfunction "2_2") (pintype "passive"))
      (node (ref "IC2") (pin "C2") (pinfunction "VDD_C2") (pintype "bidirectional"))
      (node (ref "Q1") (pin "2") (pinfunction "S_2") (pintype "bidirectional"))
      (node (ref "R5") (pin "2") (pinfunction "2_2") (pintype "bidirectional"))
      (node (ref "R7") (pin "2") (pinfunction "2_2") (pintype "bidirectional"))
      (node (ref "R8") (pin "2") (pinfunction "2_2") (pintype "bidirectional"))
      (node (ref "R_PWR_EPD") (pin "2") (pinfunction "2_2") (pintype "bidirectional"))
    )
    (net (code "2") (name "3V3{slash}2.4A") (class "Default")
      (node (ref "C12") (pin "1") (pinfunction "1_1") (pintype "passive"))
      (node (ref "C14") (pin "1") (pinfunction "1_1") (pintype "passive"))
      (node (ref "C19") (pin "1") (pinfunction "1_1") (pintype "passive"))
      (node (ref "C25") (pin "1") (pinfunction "1_1") (pintype "passive"))
      (node (ref "C33") (pin "1") (pinfunction "1_1") (pintype "passive"))
      (node (ref "C6") (pin "1") (pinfunction "1_1") (pintype "passive"))
      (node (ref "C7") (pin "1") (pinfunction "1_1") (pintype "passive"))
      (node (ref "C8") (pin "1") (pinfunction "1_1") (pintype "passive"))
      (node (ref "IC3") (pin "10") (pinfunction "CSB_10") (pintype "bidirectional"))
      (node (ref "IC3") (pin "3") (pinfunction "VDDIO_3") (pintype "bidirectional"))
      (node (ref "IC3") (pin "7") (pinfunction "VDD_7") (pintype "bidirectional"))
      (node (ref "IC9") (pin "E3") (pinfunction "VOUT_2_E3") (pintype "bidirectional"))
      (node (ref "J2") (pin "1") (pinfunction "1_1") (pintype "bidirectional"))
      (node (ref "R17") (pin "1") (pinfunction "1_1") (pintype "bidirectional"))
      (node (ref "R18") (pin "1") (pinfunction "1_1") (pintype "bidirectional"))
      (node (ref "TP_3.3V") (pin "TP") (pinfunction "TP_TP") (pintype "input"))
      (node (ref "TP_3V3") (pin "TP") (pinfunction "TP_TP") (pintype "input"))
      (node (ref "U1") (pin "P$A22") (pinfunction "VDD_P$A22") (pintype "power_in"))
      (node (ref "U1") (pin "P$AD14") (pinfunction "VDD_P$AD14") (pintype "power_in"))
      (node (ref "U1") (pin "P$AD23") (pinfunction "VDD_P$AD23") (pintype "power_in"))
      (node (ref "U1") (pin "P$B1") (pinfunction "VDD_P$B1") (pintype "power_in"))
      (node (ref "U1") (pin "P$W1") (pinfunction "VDD_P$W1") (pintype "power_in"))
      (node (ref "U1") (pin "P$Y2") (pinfunction "VDDH_P$Y2") (pintype "power_in"))
    )
    (net (code "3") (name "ALERT") (class "Default")
      (node (ref "U1") (pin "P$J24") (pinfunction "P0.10/NFC2_P$J24") (pintype "bidirectional"))
      (node (ref "U3") (pin "5") (pinfunction "~{ALERT}_5") (pintype "output"))
    )
    (net (code "4") (name "D+") (class "Default")
      (node (ref "D3") (pin "4") (pinfunction "I/O2_2_4") (pintype "bidirectional"))
      (node (ref "U1") (pin "P$AD6") (pinfunction "D+_P$AD6") (pintype "bidirectional"))
    )
    (net (code "5") (name "D-") (class "Default")
      (node (ref "D3") (pin "6") (pinfunction "I/O1_2_6") (pintype "bidirectional"))
      (node (ref "U1") (pin "P$AD4") (pinfunction "D-_P$AD4") (pintype "bidirectional"))
    )
    (net (code "6") (name "DEC1") (class "Default")
      (node (ref "C5") (pin "1") (pinfunction "1_1") (pintype "passive"))
      (node (ref "U1") (pin "P$C1") (pinfunction "DEC1_P$C1") (pintype "power_in"))
    )
    (net (code "7") (name "DEC3") (class "Default")
      (node (ref "C11") (pin "1") (pinfunction "1_1") (pintype "passive"))
      (node (ref "U1") (pin "P$D23") (pinfunction "DEC3_P$D23") (pintype "bidirectional"))
    )
    (net (code "8") (name "DEC4_6") (class "Default")
      (node (ref "C10") (pin "1") (pinfunction "1_1") (pintype "passive"))
      (node (ref "C15") (pin "1") (pinfunction "1_1") (pintype "passive"))
      (node (ref "C16") (pin "1") (pinfunction "1_1") (pintype "passive"))
      (node (ref "L3") (pin "1") (pinfunction "1_1") (pintype "passive"))
      (node (ref "U1") (pin "P$B5") (pinfunction "DEC4_P$B5") (pintype "power_in"))
      (node (ref "U1") (pin "P$E24") (pinfunction "DEC6_P$E24") (pintype "bidirectional"))
    )
    (net (code "9") (name "DN") (class "Default")
      (node (ref "D3") (pin "1") (pinfunction "I/O1_1_1") (pintype "bidirectional"))
      (node (ref "J4") (pin "A7") (pinfunction "DN1_A7") (pintype "bidirectional"))
      (node (ref "J4") (pin "B7") (pinfunction "DN2_B7") (pintype "bidirectional"))
    )
    (net (code "10") (name "DP") (class "Default")
      (node (ref "D3") (pin "3") (pinfunction "I/O2_1_3") (pintype "bidirectional"))
      (node (ref "J4") (pin "A6") (pinfunction "DP1_A6") (pintype "bidirectional"))
      (node (ref "J4") (pin "B6") (pinfunction "DP2_B6") (pintype "bidirectional"))
    )
    (net (code "11") (name "EPD_3V3") (class "Default")
      (node (ref "C1-EP-DR") (pin "1") (pinfunction "1_1") (pintype "passive"))
      (node (ref "EPD_C5") (pin "2") (pinfunction "2_2") (pintype "passive"))
      (node (ref "J1") (pin "15") (pinfunction "15_15") (pintype "bidirectional"))
      (node (ref "J1") (pin "16") (pinfunction "16_16") (pintype "bidirectional"))
      (node (ref "L5") (pin "2") (pinfunction "2_2") (pintype "passive"))
      (node (ref "Q1") (pin "3") (pinfunction "D_3") (pintype "bidirectional"))
    )
    (net (code "12") (name "EPD_BUSY") (class "Default")
      (node (ref "J1") (pin "9") (pinfunction "9_9") (pintype "bidirectional"))
      (node (ref "U1") (pin "P$AD12") (pinfunction "P0.17_P$AD12") (pintype "bidirectional"))
    )
    (net (code "13") (name "EPD_CS") (class "Default")
      (node (ref "J1") (pin "12") (pinfunction "12_12") (pintype "bidirectional"))
      (node (ref "U1") (pin "P$K2") (pinfunction "P0.05/AIN3_P$K2") (pintype "bidirectional"))
    )
    (net (code "14") (name "EPD_DC") (class "Default")
      (node (ref "J1") (pin "11") (pinfunction "11_11") (pintype "bidirectional"))
      (node (ref "U1") (pin "P$AD10") (pinfunction "P0.15_P$AD10") (pintype "bidirectional"))
    )
    (net (code "15") (name "EPD_RST") (class "Default")
      (node (ref "J1") (pin "10") (pinfunction "10_10") (pintype "bidirectional"))
      (node (ref "U1") (pin "P$AC11") (pinfunction "P0.16_P$AC11") (pintype "bidirectional"))
    )
    (net (code "16") (name "GDR") (class "Default")
      (node (ref "J1") (pin "2") (pinfunction "2_2") (pintype "bidirectional"))
      (node (ref "Q3") (pin "1") (pinfunction "G_1") (pintype "bidirectional"))
      (node (ref "R2_EP_DR") (pin "2") (pinfunction "2_2") (pintype "bidirectional"))
    )
    (net (code "17") (name "GND") (class "Default")
      (node (ref "C1") (pin "2") (pinfunction "2_2") (pintype "passive"))
      (node (ref "C1-EP-DR") (pin "2") (pinfunction "2_2") (pintype "passive"))
      (node (ref "C10") (pin "2") (pinfunction "2_2") (pintype "passive"))
      (node (ref "C11") (pin "2") (pinfunction "2_2") (pintype "passive"))
      (node (ref "C12") (pin "2") (pinfunction "2_2") (pintype "passive"))
      (node (ref "C13") (pin "2") (pinfunction "2_2") (pintype "passive"))
      (node (ref "C14") (pin "2") (pinfunction "2_2") (pintype "passive"))
      (node (ref "C15") (pin "2") (pinfunction "2_2") (pintype "passive"))
      (node (ref "C16") (pin "2") (pinfunction "2_2") (pintype "passive"))
      (node (ref "C17") (pin "1") (pinfunction "1_1") (pintype "passive"))
      (node (ref "C18") (pin "1") (pinfunction "1_1") (pintype "passive"))
      (node (ref "C19") (pin "2") (pinfunction "2_2") (pintype "passive"))
      (node (ref "C2") (pin "2") (pinfunction "2_2") (pintype "passive"))
      (node (ref "C20") (pin "2") (pinfunction "2_2") (pintype "passive"))
      (node (ref "C21") (pin "2") (pinfunction "2_2") (pintype "passive"))
      (node (ref "C22") (pin "2") (pinfunction "2_2") (pintype "passive"))
      (node (ref "C23") (pin "2") (pinfunction "2_2") (pintype "passive"))
      (node (ref "C24") (pin "1") (pinfunction "1_1") (pintype "passive"))
      (node (ref "C25") (pin "2") (pinfunction "2_2") (pintype "passive"))
      (node (ref "C27") (pin "1") (pinfunction "1_1") (pintype "passive"))
      (node (ref "C29") (pin "1") (pinfunction "1_1") (pintype "passive"))
      (node (ref "C3") (pin "2") (pinfunction "2_2") (pintype "passive"))
      (node (ref "C30") (pin "1") (pinfunction "1_1") (pintype "passive"))
      (node (ref "C31") (pin "1") (pinfunction "1_1") (pintype "passive"))
      (node (ref "C32") (pin "2") (pinfunction "2_2") (pintype "passive"))
      (node (ref "C33") (pin "2") (pinfunction "2_2") (pintype "passive"))
      (node (ref "C34") (pin "1") (pinfunction "1_1") (pintype "passive"))
      (node (ref "C37") (pin "1") (pinfunction "1_1") (pintype "passive"))
      (node (ref "C38") (pin "1") (pinfunction "1_1") (pintype "passive"))
      (node (ref "C39") (pin "2") (pinfunction "2_2") (pintype "passive"))
      (node (ref "C4") (pin "2") (pinfunction "2_2") (pintype "passive"))
      (node (ref "C42") (pin "2") (pinfunction "2_2") (pintype "passive"))
      (node (ref "C43") (pin "2") (pinfunction "2_2") (pintype "passive"))
      (node (ref "C5") (pin "2") (pinfunction "2_2") (pintype "passive"))
      (node (ref "C6") (pin "2") (pinfunction "2_2") (pintype "passive"))
      (node (ref "C7") (pin "2") (pinfunction "2_2") (pintype "passive"))
      (node (ref "C8") (pin "2") (pinfunction "2_2") (pintype "passive"))
      (node (ref "C9") (pin "2") (pinfunction "2_2") (pintype "passive"))
      (node (ref "D3") (pin "2") (pinfunction "GND_2") (pintype "bidirectional"))
      (node (ref "D4") (pin "1") (pinfunction "K_1") (pintype "bidirectional"))
      (node (ref "EPD_C1") (pin "2") (pinfunction "2_2") (pintype "passive"))
      (node (ref "EPD_C10") (pin "1") (pinfunction "1_1") (pintype "passive"))
      (node (ref "EPD_C11") (pin "1") (pinfunction "1_1") (pintype "passive"))
      (node (ref "EPD_C12") (pin "1") (pinfunction "1_1") (pintype "passive"))
      (node (ref "EPD_C2") (pin "2") (pinfunction "2_2") (pintype "passive"))
      (node (ref "EPD_C5") (pin "1") (pinfunction "1_1") (pintype "passive"))
      (node (ref "EPD_C6") (pin "1") (pinfunction "1_1") (pintype "passive"))
      (node (ref "EPD_C7") (pin "1") (pinfunction "1_1") (pintype "passive"))
      (node (ref "EPD_C8") (pin "1") (pinfunction "1_1") (pintype "passive"))
      (node (ref "EPD_C9") (pin "1") (pinfunction "1_1") (pintype "passive"))
      (node (ref "IC1") (pin "D2") (pinfunction "GND_D2") (pintype "bidirectional"))
      (node (ref "IC2") (pin "B1") (pinfunction "IN/TRIG_B1") (pintype "bidirectional"))
      (node (ref "IC2") (pin "B3") (pinfunction "GND_B3") (pintype "bidirectional"))
      (node (ref "IC3") (pin "8") (pinfunction "GNDIO_8") (pintype "bidirectional"))
      (node (ref "IC3") (pin "9") (pinfunction "GND_9") (pintype "bidirectional"))
      (node (ref "IC9") (pin "B1") (pinfunction "VSEL_B1") (pintype "bidirectional"))
      (node (ref "IC9") (pin "C1") (pinfunction "AGND_C1") (pintype "bidirectional"))
      (node (ref "IC9") (pin "C2") (pinfunction "PGND_1_C2") (pintype "bidirectional"))
      (node (ref "IC9") (pin "C3") (pinfunction "PGND_2_C3") (pintype "bidirectional"))
      (node (ref "J1") (pin "17") (pinfunction "17_17") (pintype "bidirectional"))
      (node (ref "J1") (pin "8") (pinfunction "8_8") (pintype "bidirectional"))
      (node (ref "J1") (pin "MP1") (pinfunction "MP1_MP1") (pintype "bidirectional"))
      (node (ref "J1") (pin "MP2") (pinfunction "MP2_MP2") (pintype "bidirectional"))
      (node (ref "J2") (pin "3") (pinfunction "3_3") (pintype "bidirectional"))
      (node (ref "J2") (pin "5") (pinfunction "5_5") (pintype "bidirectional"))
      (node (ref "J4") (pin "A12_B1") (pinfunction "GND_A12_B1") (pintype "power_in"))
      (node (ref "J4") (pin "A1_B12") (pinfunction "GND_A1_B12") (pintype "power_in"))
      (node (ref "J4") (pin "SH1") (pinfunction "SHIELD_SH1") (pintype "passive"))
      (node (ref "J4") (pin "SH2") (pinfunction "SHIELD_SH2") (pintype "passive"))
      (node (ref "J4") (pin "SH3") (pinfunction "SHIELD_SH3") (pintype "passive"))
      (node (ref "J4") (pin "SH4") (pinfunction "SHIELD_SH4") (pintype "passive"))
      (node (ref "R1_TYPE_SEL") (pin "1") (pinfunction "1_1") (pintype "bidirectional"))
      (node (ref "R1_USB") (pin "1") (pinfunction "1_1") (pintype "bidirectional"))
      (node (ref "R2_EP_DR") (pin "1") (pinfunction "1_1") (pintype "bidirectional"))
      (node (ref "R2_USB") (pin "2") (pinfunction "2_2") (pintype "bidirectional"))
      (node (ref "R3") (pin "1") (pinfunction "1_1") (pintype "bidirectional"))
      (node (ref "R9") (pin "1") (pinfunction "1_1") (pintype "bidirectional"))
      (node (ref "SJ1") (pin "1") (pinfunction "1_1") (pintype "passive"))
      (node (ref "SW_DN") (pin "1") (pinfunction "1_1") (pintype "passive"))
      (node (ref "SW_ENT") (pin "1") (pinfunction "1_1") (pintype "passive"))
      (node (ref "SW_UP") (pin "1") (pinfunction "1_1") (pintype "passive"))
      (node (ref "TP_BAT_GND") (pin "TP") (pinfunction "TP_TP") (pintype "input"))
      (node (ref "TP_GND") (pin "TP") (pinfunction "TP_TP") (pintype "input"))
      (node (ref "U1") (pin "P$74") (pinfunction "VSS_PAD_P$74") (pintype "bidirectional"))
      (node (ref "U1") (pin "P$75") (pinfunction "VSS_PAD_P$75") (pintype "bidirectional"))
      (node (ref "U1") (pin "P$76") (pinfunction "VSS_PAD_P$76") (pintype "bidirectional"))
      (node (ref "U1") (pin "P$77") (pinfunction "VSS_PAD_P$77") (pintype "bidirectional"))
      (node (ref "U1") (pin "P$78") (pinfunction "VSS_PAD_P$78") (pintype "bidirectional"))
      (node (ref "U1") (pin "P$79") (pinfunction "VSS_PAD_P$79") (pintype "bidirectional"))
      (node (ref "U1") (pin "P$80") (pinfunction "VSS_PAD_P$80") (pintype "bidirectional"))
      (node (ref "U1") (pin "P$81") (pinfunction "VSS_PAD_P$81") (pintype "bidirectional"))
      (node (ref "U1") (pin "P$82") (pinfunction "VSS_PAD_P$82") (pintype "bidirectional"))
      (node (ref "U1") (pin "P$83") (pinfunction "VSS_PAD_P$83") (pintype "bidirectional"))
      (node (ref "U1") (pin "P$84") (pinfunction "VSS_PAD_P$84") (pintype "bidirectional"))
      (node (ref "U1") (pin "P$85") (pinfunction "VSS_PAD_P$85") (pintype "bidirectional"))
      (node (ref "U1") (pin "P$86") (pinfunction "VSS_PAD_P$86") (pintype "bidirectional"))
      (node (ref "U1") (pin "P$87") (pinfunction "VSS_PAD_P$87") (pintype "bidirectional"))
      (node (ref "U1") (pin "P$88") (pinfunction "VSS_PAD_P$88") (pintype "bidirectional"))
      (node (ref "U1") (pin "P$89") (pinfunction "VSS_PAD_P$89") (pintype "bidirectional"))
      (node (ref "U1") (pin "P$90") (pinfunction "VSS_PAD_P$90") (pintype "bidirectional"))
      (node (ref "U1") (pin "P$B7") (pinfunction "VSS_P$B7") (pintype "power_in"))
      (node (ref "U1") (pin "P$F23") (pinfunction "VSS_PA_P$F23") (pintype "bidirectional"))
      (node (ref "U3") (pin "1") (pinfunction "CTG_1") (pintype "power_in"))
      (node (ref "U3") (pin "4") (pinfunction "GND_4") (pintype "power_in"))
      (node (ref "U3") (pin "6") (pinfunction "QSTRT_6") (pintype "input"))
      (node (ref "U3") (pin "9") (pinfunction "EP_9") (pintype "power_in"))
      (node (ref "X1") (pin "2") (pinfunction "2_2") (pintype "passive"))
      (node (ref "X1") (pin "4") (pinfunction "4_4") (pintype "passive"))
    )
    (net (code "18") (name "HAPTIC_EN") (class "Default")
      (node (ref "IC2") (pin "A1") (pinfunction "EN_A1") (pintype "bidirectional"))
      (node (ref "U1") (pin "P$U1") (pinfunction "P0.12_P$U1") (pintype "bidirectional"))
    )
    (net (code "19") (name "IMU_INT1") (class "Default")
      (node (ref "IC3") (pin "5") (pinfunction "INT1_5") (pintype "bidirectional"))
      (node (ref "U1") (pin "P$N1") (pinfunction "P0.08_P$N1") (pintype "bidirectional"))
    )
    (net (code "20") (name "IMU_INT2") (class "Default")
      (node (ref "IC3") (pin "6") (pinfunction "INT2_6") (pintype "bidirectional"))
      (node (ref "U1") (pin "P$P2") (pinfunction "P1.08_P$P2") (pintype "bidirectional"))
    )
    (net (code "21") (name "LX1") (class "Default")
      (node (ref "IC9") (pin "B2") (pinfunction "SW1_1_B2") (pintype "bidirectional"))
      (node (ref "IC9") (pin "B3") (pinfunction "SW1_2_B3") (pintype "bidirectional"))
      (node (ref "L7") (pin "1") (pinfunction "1_1") (pintype "bidirectional"))
    )
    (net (code "22") (name "LX2") (class "Default")
      (node (ref "IC9") (pin "D2") (pinfunction "SW2_1_D2") (pintype "bidirectional"))
      (node (ref "IC9") (pin "D3") (pinfunction "SW2_2_D3") (pintype "bidirectional"))
      (node (ref "L7") (pin "2") (pinfunction "2_2") (pintype "bidirectional"))
    )
    (net (code "23") (name "MOSI") (class "Default")
      (node (ref "J1") (pin "14") (pinfunction "14_14") (pintype "bidirectional"))
      (node (ref "U1") (pin "P$B13") (pinfunction "P0.03/AIN1_P$B13") (pintype "bidirectional"))
    )
    (net (code "24") (name "Net-(D2-K)") (class "Default")
      (node (ref "C2-EP-DR") (pin "1") (pinfunction "1_1") (pintype "passive"))
      (node (ref "D2") (pin "1") (pinfunction "K_1") (pintype "bidirectional"))
      (node (ref "D4") (pin "2") (pinfunction "A_2") (pintype "bidirectional"))
    )
    (net (code "25") (name "Net-(D5-A)") (class "Default")
      (node (ref "C2-EP-DR") (pin "2") (pinfunction "2_2") (pintype "passive"))
      (node (ref "D5") (pin "2") (pinfunction "A_2") (pintype "bidirectional"))
      (node (ref "L5") (pin "1") (pinfunction "1_1") (pintype "passive"))
      (node (ref "Q3") (pin "3") (pinfunction "D_3") (pintype "bidirectional"))
    )
    (net (code "26") (name "Net-(EPD_C1-Pad1)") (class "Default")
      (node (ref "EPD_C1") (pin "1") (pinfunction "1_1") (pintype "passive"))
      (node (ref "J1") (pin "5") (pinfunction "5_5") (pintype "bidirectional"))
    )
    (net (code "27") (name "Net-(EPD_C2-Pad1)") (class "Default")
      (node (ref "EPD_C2") (pin "1") (pinfunction "1_1") (pintype "passive"))
      (node (ref "J1") (pin "4") (pinfunction "4_4") (pintype "bidirectional"))
    )
    (net (code "28") (name "Net-(EPD_C6-Pad2)") (class "Default")
      (node (ref "EPD_C6") (pin "2") (pinfunction "2_2") (pintype "passive"))
      (node (ref "J1") (pin "18") (pinfunction "18_18") (pintype "bidirectional"))
    )
    (net (code "29") (name "Net-(EPD_C7-Pad2)") (class "Default")
      (node (ref "EPD_C7") (pin "2") (pinfunction "2_2") (pintype "passive"))
      (node (ref "J1") (pin "19") (pinfunction "19_19") (pintype "bidirectional"))
    )
    (net (code "30") (name "Net-(EPD_C8-Pad2)") (class "Default")
      (node (ref "EPD_C8") (pin "2") (pinfunction "2_2") (pintype "passive"))
      (node (ref "J1") (pin "20") (pinfunction "20_20") (pintype "bidirectional"))
    )
    (net (code "31") (name "Net-(EPD_C10-Pad2)") (class "Default")
      (node (ref "EPD_C10") (pin "2") (pinfunction "2_2") (pintype "passive"))
      (node (ref "J1") (pin "22") (pinfunction "22_22") (pintype "bidirectional"))
    )
    (net (code "32") (name "Net-(EPD_C12-Pad2)") (class "Default")
      (node (ref "EPD_C12") (pin "2") (pinfunction "2_2") (pintype "passive"))
      (node (ref "J1") (pin "24") (pinfunction "24_24") (pintype "bidirectional"))
    )
    (net (code "33") (name "Net-(IC1-TS{slash}MR)") (class "Default")
      (node (ref "IC1") (pin "D1") (pinfunction "TS/MR_D1") (pintype "bidirectional"))
      (node (ref "R9") (pin "2") (pinfunction "2_2") (pintype "bidirectional"))
    )
    (net (code "34") (name "Net-(IC2-REG)") (class "Default")
      (node (ref "C32") (pin "1") (pinfunction "1_1") (pintype "passive"))
      (node (ref "IC2") (pin "A2") (pinfunction "REG_A2") (pintype "bidirectional"))
    )
    (net (code "35") (name "Net-(IC3-SDO)") (class "Default")
      (node (ref "IC3") (pin "1") (pinfunction "SDO_1") (pintype "bidirectional"))
      (node (ref "R3") (pin "2") (pinfunction "2_2") (pintype "bidirectional"))
    )
    (net (code "36") (name "Net-(IC9-SCL)") (class "Default")
      (node (ref "IC9") (pin "D1") (pinfunction "SCL_D1") (pintype "bidirectional"))
      (node (ref "R4") (pin "2") (pinfunction "2_2") (pintype "bidirectional"))
    )
    (net (code "37") (name "Net-(IC9-SDA)") (class "Default")
      (node (ref "IC9") (pin "E1") (pinfunction "SDA_E1") (pintype "bidirectional"))
      (node (ref "R2") (pin "2") (pinfunction "2_2") (pintype "bidirectional"))
    )
    (net (code "38") (name "Net-(J4-CC1)") (class "Default")
      (node (ref "J4") (pin "A5") (pinfunction "CC1_A5") (pintype "bidirectional"))
      (node (ref "R1_USB") (pin "2") (pinfunction "2_2") (pintype "bidirectional"))
    )
    (net (code "39") (name "Net-(J4-CC2)") (class "Default")
      (node (ref "J4") (pin "B5") (pinfunction "CC2_B5") (pintype "bidirectional"))
      (node (ref "R2_USB") (pin "1") (pinfunction "1_1") (pintype "bidirectional"))
    )
    (net (code "40") (name "Net-(L2-Pad1)") (class "Default")
      (node (ref "L2") (pin "1") (pinfunction "1_1") (pintype "passive"))
      (node (ref "L3") (pin "2") (pinfunction "2_2") (pintype "passive"))
    )
    (net (code "41") (name "Net-(R1_EP_DR-Pad1)") (class "Default")
      (node (ref "R1_EP_DR") (pin "1") (pinfunction "1_1") (pintype "bidirectional"))
      (node (ref "R1_TYPE_SEL") (pin "2") (pinfunction "2_2") (pintype "bidirectional"))
      (node (ref "SJ1") (pin "2") (pinfunction "2_2") (pintype "passive"))
    )
    (net (code "42") (name "Net-(U1-ANT)") (class "Default")
      (node (ref "C3") (pin "1") (pinfunction "1_1") (pintype "passive"))
      (node (ref "L1") (pin "1") (pinfunction "1_1") (pintype "passive"))
      (node (ref "U1") (pin "P$H23") (pinfunction "ANT_P$H23") (pintype "bidirectional"))
    )
    (net (code "43") (name "Net-(U1-DCC)") (class "Default")
      (node (ref "L2") (pin "2") (pinfunction "2_2") (pintype "passive"))
      (node (ref "U1") (pin "P$B3") (pinfunction "DCC_P$B3") (pintype "output"))
    )
    (net (code "44") (name "Net-(U1-DEC2)") (class "Default")
      (node (ref "C13") (pin "1") (pinfunction "1_1") (pintype "passive"))
      (node (ref "U1") (pin "P$A18") (pinfunction "DEC2_P$A18") (pintype "bidirectional"))
    )
    (net (code "45") (name "Net-(U1-DEC3V3)") (class "Default")
      (node (ref "C20") (pin "1") (pinfunction "1_1") (pintype "passive"))
      (node (ref "U1") (pin "P$AC5") (pinfunction "DEC3V3_P$AC5") (pintype "bidirectional"))
    )
    (net (code "46") (name "Net-(U1-DEC5)") (class "Default")
      (node (ref "C9") (pin "1") (pinfunction "1_1") (pintype "passive"))
      (node (ref "U1") (pin "P$N24") (pinfunction "DEC5_P$N24") (pintype "bidirectional"))
    )
    (net (code "47") (name "Net-(U1-P0.00{slash}XL1)") (class "Default")
      (node (ref "C17") (pin "2") (pinfunction "2_2") (pintype "passive"))
      (node (ref "U1") (pin "P$D2") (pinfunction "P0.00/XL1_P$D2") (pintype "bidirectional"))
      (node (ref "X2") (pin "1") (pinfunction "1_1") (pintype "passive"))
    )
    (net (code "48") (name "Net-(U1-P0.01{slash}XL2)") (class "Default")
      (node (ref "C18") (pin "2") (pinfunction "2_2") (pintype "passive"))
      (node (ref "U1") (pin "P$F2") (pinfunction "P0.01/XL2_P$F2") (pintype "bidirectional"))
      (node (ref "X2") (pin "2") (pinfunction "2_2") (pintype "passive"))
    )
    (net (code "49") (name "Net-(U1-XC1)") (class "Default")
      (node (ref "C1") (pin "1") (pinfunction "1_1") (pintype "passive"))
      (node (ref "U1") (pin "P$B24") (pinfunction "XC1_P$B24") (pintype "input"))
      (node (ref "X1") (pin "1") (pinfunction "1_1") (pintype "passive"))
    )
    (net (code "50") (name "Net-(U1-XC2)") (class "Default")
      (node (ref "C2") (pin "1") (pinfunction "1_1") (pintype "passive"))
      (node (ref "U1") (pin "P$A23") (pinfunction "XC2_P$A23") (pintype "output"))
      (node (ref "X1") (pin "3") (pinfunction "3_3") (pintype "passive"))
    )
    (net (code "51") (name "OUT+") (class "Default")
      (node (ref "IC2") (pin "A3") (pinfunction "OUT+_A3") (pintype "bidirectional"))
      (node (ref "TP_OP") (pin "TP") (pinfunction "TP_TP") (pintype "input"))
    )
    (net (code "52") (name "OUT-") (class "Default")
      (node (ref "IC2") (pin "C3") (pinfunction "OUT-_C3") (pintype "bidirectional"))
      (node (ref "TP_ON") (pin "TP") (pinfunction "TP_TP") (pintype "input"))
    )
    (net (code "53") (name "P0.04") (class "Default")
      (node (ref "U1") (pin "P$J1") (pinfunction "P0.04/AIN2_P$J1") (pintype "bidirectional"))
    )
    (net (code "54") (name "P0.09") (class "Default")
      (node (ref "U1") (pin "P$L24") (pinfunction "P0.09/NFC1_P$L24") (pintype "bidirectional"))
    )
    (net (code "55") (name "P0.13{slash}1.5D") (class "Default")
      (node (ref "C30") (pin "2") (pinfunction "2_2") (pintype "passive"))
      (node (ref "R5") (pin "1") (pinfunction "1_1") (pintype "bidirectional"))
      (node (ref "SW_UP") (pin "2") (pinfunction "2_2") (pintype "passive"))
    )
    (net (code "56") (name "P0.13{slash}2.6C") (class "Default")
      (node (ref "U1") (pin "P$AD8") (pinfunction "P0.13_P$AD8") (pintype "bidirectional"))
    )
    (net (code "57") (name "P0.14{slash}1.5D") (class "Default")
      (node (ref "C31") (pin "2") (pinfunction "2_2") (pintype "passive"))
      (node (ref "R8") (pin "1") (pinfunction "1_1") (pintype "bidirectional"))
      (node (ref "SW_ENT") (pin "2") (pinfunction "2_2") (pintype "passive"))
    )
    (net (code "58") (name "P0.14{slash}2.7C") (class "Default")
      (node (ref "U1") (pin "P$AC9") (pinfunction "P0.14_P$AC9") (pintype "bidirectional"))
    )
    (net (code "59") (name "P0.19") (class "Default")
      (node (ref "U1") (pin "P$AC15") (pinfunction "P0.19_P$AC15") (pintype "bidirectional"))
    )
    (net (code "60") (name "P0.20") (class "Default")
      (node (ref "U1") (pin "P$AD16") (pinfunction "P0.20_P$AD16") (pintype "bidirectional"))
    )
    (net (code "61") (name "P0.21") (class "Default")
      (node (ref "U1") (pin "P$AC17") (pinfunction "P0.21_P$AC17") (pintype "bidirectional"))
    )
    (net (code "62") (name "P0.22") (class "Default")
      (node (ref "U1") (pin "P$AD18") (pinfunction "P0.22_P$AD18") (pintype "bidirectional"))
    )
    (net (code "63") (name "P0.23") (class "Default")
      (node (ref "U1") (pin "P$AC19") (pinfunction "P0.23_P$AC19") (pintype "bidirectional"))
    )
    (net (code "64") (name "P0.24") (class "Default")
      (node (ref "U1") (pin "P$AD20") (pinfunction "P0.24_P$AD20") (pintype "bidirectional"))
    )
    (net (code "65") (name "P0.25") (class "Default")
      (node (ref "U1") (pin "P$AC21") (pinfunction "P0.25_P$AC21") (pintype "bidirectional"))
    )
    (net (code "66") (name "P0.26") (class "Default")
      (node (ref "U1") (pin "P$G1") (pinfunction "P0.26_P$G1") (pintype "bidirectional"))
    )
    (net (code "67") (name "P0.27") (class "Default")
      (node (ref "U1") (pin "P$H2") (pinfunction "P0.27_P$H2") (pintype "bidirectional"))
    )
    (net (code "68") (name "P0.28") (class "Default")
      (node (ref "U1") (pin "P$B11") (pinfunction "P0.28/AIN4_P$B11") (pintype "bidirectional"))
    )
    (net (code "69") (name "P0.29") (class "Default")
      (node (ref "U1") (pin "P$A10") (pinfunction "P0.29/AIN5_P$A10") (pintype "bidirectional"))
    )
    (net (code "70") (name "P0.30") (class "Default")
      (node (ref "U1") (pin "P$B9") (pinfunction "P0.30/AIN6_P$B9") (pintype "bidirectional"))
    )
    (net (code "71") (name "P0.31") (class "Default")
      (node (ref "U1") (pin "P$A8") (pinfunction "P0.31/AIN7_P$A8") (pintype "bidirectional"))
    )
    (net (code "72") (name "P1.01{slash}1.6C") (class "Default")
      (node (ref "Q1") (pin "1") (pinfunction "G_1") (pintype "bidirectional"))
      (node (ref "R_PWR_EPD") (pin "1") (pinfunction "1_1") (pintype "bidirectional"))
    )
    (net (code "73") (name "P1.01{slash}2.4B") (class "Default")
      (node (ref "U1") (pin "P$Y23") (pinfunction "P1.01_P$Y23") (pintype "bidirectional"))
    )
    (net (code "74") (name "P1.02{slash}1.6C") (class "Default")
      (node (ref "C29") (pin "2") (pinfunction "2_2") (pintype "passive"))
      (node (ref "R7") (pin "1") (pinfunction "1_1") (pintype "bidirectional"))
      (node (ref "SW_DN") (pin "2") (pinfunction "2_2") (pintype "passive"))
    )
    (net (code "75") (name "P1.02{slash}2.8C") (class "Default")
      (node (ref "U1") (pin "P$W24") (pinfunction "P1.02_P$W24") (pintype "bidirectional"))
    )
    (net (code "76") (name "P1.03") (class "Default")
      (node (ref "U1") (pin "P$V23") (pinfunction "P1.03_P$V23") (pintype "bidirectional"))
    )
    (net (code "77") (name "P1.04") (class "Default")
      (node (ref "U1") (pin "P$U24") (pinfunction "P1.04_P$U24") (pintype "bidirectional"))
    )
    (net (code "78") (name "P1.05") (class "Default")
      (node (ref "U1") (pin "P$T23") (pinfunction "P1.05_P$T23") (pintype "bidirectional"))
    )
    (net (code "79") (name "P1.06") (class "Default")
      (node (ref "U1") (pin "P$R24") (pinfunction "P1.06_P$R24") (pintype "bidirectional"))
    )
    (net (code "80") (name "P1.07") (class "Default")
      (node (ref "U1") (pin "P$P23") (pinfunction "P1.07_P$P23") (pintype "bidirectional"))
    )
    (net (code "81") (name "P1.09") (class "Default")
      (node (ref "U1") (pin "P$R1") (pinfunction "P1.09_P$R1") (pintype "bidirectional"))
    )
    (net (code "82") (name "P1.10") (class "Default")
      (node (ref "U1") (pin "P$A20") (pinfunction "P1.10_P$A20") (pintype "bidirectional"))
    )
    (net (code "83") (name "P1.11") (class "Default")
      (node (ref "U1") (pin "P$B19") (pinfunction "P1.11_P$B19") (pintype "bidirectional"))
    )
    (net (code "84") (name "P1.12") (class "Default")
      (node (ref "U1") (pin "P$B17") (pinfunction "P1.12_P$B17") (pintype "bidirectional"))
    )
    (net (code "85") (name "P1.13") (class "Default")
      (node (ref "U1") (pin "P$A16") (pinfunction "P1.13_P$A16") (pintype "bidirectional"))
    )
    (net (code "86") (name "P1.14") (class "Default")
      (node (ref "U1") (pin "P$B15") (pinfunction "P1.14_P$B15") (pintype "bidirectional"))
    )
    (net (code "87") (name "P1.15") (class "Default")
      (node (ref "U1") (pin "P$A14") (pinfunction "P1.15_P$A14") (pintype "bidirectional"))
    )
    (net (code "88") (name "PMIC_INT") (class "Default")
      (node (ref "IC1") (pin "A1") (pinfunction "~{INT}_A1") (pintype "bidirectional"))
      (node (ref "U1") (pin "P$T2") (pinfunction "P0.11_P$T2") (pintype "bidirectional"))
    )
    (net (code "89") (name "PREVGH") (class "Default")
      (node (ref "D5") (pin "1") (pinfunction "K_1") (pintype "bidirectional"))
      (node (ref "EPD_C9") (pin "2") (pinfunction "2_2") (pintype "passive"))
      (node (ref "J1") (pin "21") (pinfunction "21_21") (pintype "bidirectional"))
    )
    (net (code "90") (name "PREVGL") (class "Default")
      (node (ref "D2") (pin "2") (pinfunction "A_2") (pintype "bidirectional"))
      (node (ref "EPD_C11") (pin "2") (pinfunction "2_2") (pintype "passive"))
      (node (ref "J1") (pin "23") (pinfunction "23_23") (pintype "bidirectional"))
    )
    (net (code "91") (name "RESE") (class "Default")
      (node (ref "J1") (pin "3") (pinfunction "3_3") (pintype "bidirectional"))
      (node (ref "Q3") (pin "2") (pinfunction "S_2") (pintype "bidirectional"))
      (node (ref "R1_EP_DR") (pin "2") (pinfunction "2_2") (pintype "bidirectional"))
    )
    (net (code "92") (name "RESET") (class "Default")
      (node (ref "J2") (pin "6") (pinfunction "6_6") (pintype "bidirectional"))
      (node (ref "TP_RESET") (pin "TP") (pinfunction "TP_TP") (pintype "input"))
      (node (ref "U1") (pin "P$AC13") (pinfunction "P0.18/RESET_P$AC13") (pintype "bidirectional"))
    )
    (net (code "93") (name "RF") (class "Default")
      (node (ref "ANT1") (pin "1") (pinfunction "FEED_1") (pintype "input"))
      (node (ref "C22") (pin "1") (pinfunction "1_1") (pintype "passive"))
      (node (ref "C4") (pin "1") (pinfunction "1_1") (pintype "passive"))
      (node (ref "L1") (pin "2") (pinfunction "2_2") (pintype "passive"))
    )
    (net (code "94") (name "SCK") (class "Default")
      (node (ref "J1") (pin "13") (pinfunction "13_13") (pintype "bidirectional"))
      (node (ref "U1") (pin "P$A12") (pinfunction "P0.02/AIN0_P$A12") (pintype "bidirectional"))
    )
    (net (code "95") (name "SCL{slash}1.4C") (class "Default")
      (node (ref "IC2") (pin "C1") (pinfunction "SCL_C1") (pintype "bidirectional"))
      (node (ref "U3") (pin "7") (pinfunction "SCL_7") (pintype "input"))
    )
    (net (code "96") (name "SCL{slash}2.4C") (class "Default")
      (node (ref "IC1") (pin "B1") (pinfunction "SCL_B1") (pintype "bidirectional"))
      (node (ref "IC3") (pin "12") (pinfunction "SCX_12") (pintype "bidirectional"))
      (node (ref "R17") (pin "2") (pinfunction "2_2") (pintype "bidirectional"))
      (node (ref "R4") (pin "1") (pinfunction "1_1") (pintype "bidirectional"))
      (node (ref "TP_SCL") (pin "TP") (pinfunction "TP_TP") (pintype "input"))
      (node (ref "U1") (pin "P$M2") (pinfunction "P0.07_P$M2") (pintype "bidirectional"))
    )
    (net (code "97") (name "SDA{slash}1.4C") (class "Default")
      (node (ref "IC2") (pin "B2") (pinfunction "SDA_B2") (pintype "bidirectional"))
      (node (ref "U3") (pin "8") (pinfunction "SDA_8") (pintype "bidirectional"))
    )
    (net (code "98") (name "SDA{slash}2.4C") (class "Default")
      (node (ref "IC1") (pin "C1") (pinfunction "SDA_C1") (pintype "bidirectional"))
      (node (ref "IC3") (pin "2") (pinfunction "SDX_2") (pintype "bidirectional"))
      (node (ref "R18") (pin "2") (pinfunction "2_2") (pintype "bidirectional"))
      (node (ref "R2") (pin "1") (pinfunction "1_1") (pintype "bidirectional"))
      (node (ref "TP_SDA") (pin "TP") (pinfunction "TP_TP") (pintype "input"))
      (node (ref "U1") (pin "P$L1") (pinfunction "P0.06_P$L1") (pintype "bidirectional"))
    )
    (net (code "99") (name "SWDCLK") (class "Default")
      (node (ref "J2") (pin "4") (pinfunction "4_4") (pintype "bidirectional"))
      (node (ref "TP_SWDCLK") (pin "TP") (pinfunction "TP_TP") (pintype "input"))
      (node (ref "U1") (pin "P$AA24") (pinfunction "SWDCLK_P$AA24") (pintype "input"))
    )
    (net (code "100") (name "SWDIO") (class "Default")
      (node (ref "J2") (pin "2") (pinfunction "2_2") (pintype "bidirectional"))
      (node (ref "TP_SWDIO") (pin "TP") (pinfunction "TP_TP") (pintype "input"))
      (node (ref "U1") (pin "P$AC24") (pinfunction "SWDIO_P$AC24") (pintype "bidirectional"))
    )
    (net (code "101") (name "SWO") (class "Default")
      (node (ref "TP_SWO") (pin "TP") (pinfunction "TP_TP") (pintype "input"))
      (node (ref "U1") (pin "P$AD22") (pinfunction "P1.00_P$AD22") (pintype "bidirectional"))
    )
    (net (code "102") (name "VBAT{slash}1.2A") (class "Default")
      (node (ref "C27") (pin "2") (pinfunction "2_2") (pintype "passive"))
      (node (ref "TP_VBAT") (pin "TP") (pinfunction "TP_TP") (pintype "input"))
      (node (ref "U3") (pin "2") (pinfunction "CELL_2") (pintype "power_in"))
      (node (ref "U3") (pin "3") (pinfunction "VDD_3") (pintype "power_in"))
    )
    (net (code "103") (name "VBAT{slash}2.5C") (class "Default")
      (node (ref "C37") (pin "2") (pinfunction "2_2") (pintype "passive"))
      (node (ref "IC1") (pin "C2") (pinfunction "BAT_C2") (pintype "bidirectional"))
    )
    (net (code "104") (name "VBUS{slash}1.5D") (class "Default")
      (node (ref "C42") (pin "1") (pinfunction "1_1") (pintype "passive"))
      (node (ref "C43") (pin "1") (pinfunction "1_1") (pintype "passive"))
      (node (ref "D3") (pin "5") (pinfunction "VBUS_5") (pintype "bidirectional"))
      (node (ref "J4") (pin "A4_B9") (pinfunction "VBUS_A4_B9") (pintype "power_in"))
      (node (ref "J4") (pin "A9_B4") (pinfunction "VBUS_A9_B4") (pintype "power_in"))
    )
    (net (code "105") (name "VBUS{slash}2.6D") (class "Default")
      (node (ref "C21") (pin "1") (pinfunction "1_1") (pintype "passive"))
      (node (ref "C38") (pin "2") (pinfunction "2_2") (pintype "passive"))
      (node (ref "IC1") (pin "A2") (pinfunction "IN_A2") (pintype "bidirectional"))
      (node (ref "U1") (pin "P$AD2") (pinfunction "VBUS_P$AD2") (pintype "power_in"))
    )
    (net (code "106") (name "VREG") (class "Default")
      (node (ref "C23") (pin "1") (pinfunction "1_1") (pintype "passive"))
      (node (ref "C24") (pin "2") (pinfunction "2_2") (pintype "passive"))
      (node (ref "C39") (pin "1") (pinfunction "1_1") (pintype "passive"))
      (node (ref "IC1") (pin "B2") (pinfunction "SYS_B2") (pintype "bidirectional"))
      (node (ref "IC9") (pin "A1") (pinfunction "EN_A1") (pintype "bidirectional"))
      (node (ref "IC9") (pin "A2") (pinfunction "VIN_1_A2") (pintype "bidirectional"))
      (node (ref "IC9") (pin "A3") (pinfunction "VIN_2_A3") (pintype "bidirectional"))
      (node (ref "TP_VREG") (pin "TP") (pinfunction "TP_TP") (pintype "input"))
    )
    (net (code "107") (name "unconnected-(ANT1-NC-Pad2)") (class "Default")
      (node (ref "ANT1") (pin "2") (pinfunction "NC_2") (pintype "no_connect"))
    )
    (net (code "108") (name "unconnected-(IC3-ASCL-Pad11)") (class "Default")
      (node (ref "IC3") (pin "11") (pinfunction "ASCL_11") (pintype "bidirectional"))
    )
    (net (code "109") (name "unconnected-(IC3-ASDA-Pad4)") (class "Default")
      (node (ref "IC3") (pin "4") (pinfunction "ASDA_4") (pintype "bidirectional"))
    )
    (net (code "110") (name "unconnected-(IC9-VOUT_1-PadE2)") (class "Default")
      (node (ref "IC9") (pin "E2") (pinfunction "VOUT_1_E2") (pintype "bidirectional"))
    )
    (net (code "111") (name "unconnected-(J1-Pad1)") (class "Default")
      (node (ref "J1") (pin "1") (pinfunction "1_1") (pintype "bidirectional"))
    )
    (net (code "112") (name "unconnected-(J1-Pad6)") (class "Default")
      (node (ref "J1") (pin "6") (pinfunction "6_6") (pintype "bidirectional"))
    )
    (net (code "113") (name "unconnected-(J1-Pad7)") (class "Default")
      (node (ref "J1") (pin "7") (pinfunction "7_7") (pintype "bidirectional"))
    )
    (net (code "114") (name "unconnected-(J4-SBU1-PadA8)") (class "Default")
      (node (ref "J4") (pin "A8") (pinfunction "SBU1_A8") (pintype "bidirectional"))
    )
    (net (code "115") (name "unconnected-(J4-SBU2-PadB8)") (class "Default")
      (node (ref "J4") (pin "B8") (pinfunction "SBU2_B8") (pintype "bidirectional"))
    )
    (net (code "116") (name "unconnected-(U1-DCCH-PadP$AB2)") (class "Default")
      (node (ref "U1") (pin "P$AB2") (pinfunction "DCCH_P$AB2") (pintype "bidirectional"))
    )
  )
)
